# IsolatedPeltierDriver.net
KiCad netlist of a schematic drawn in Altium Designer
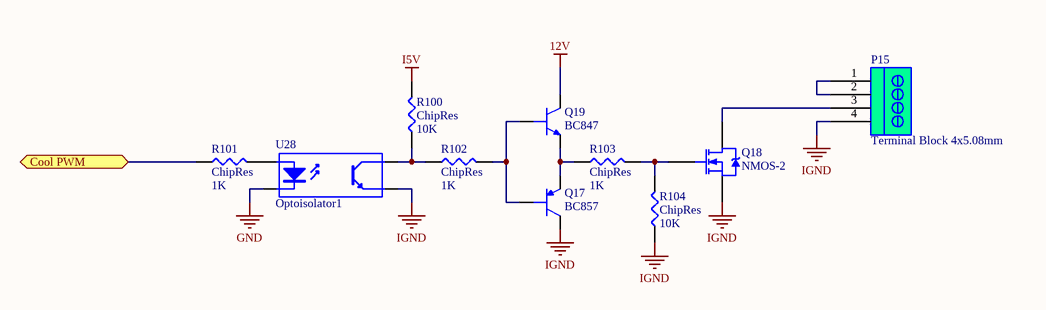
[diagram p0: IsolatedPeltierDriver.SchDoc]

(export (version "E")
  (design (tool "Eeschema 10.0.6"))
  (components
    (comp (ref "P15")
      (value "Terminal Block 4x5.08mm")
      (footprint "Socket 4x5.08")
      (description "Terminal Block Socket Right Angle 4x5.08mm 2-Wall")
      (libsource (lib "IndustrialConnectors") (part "Socket_4x5.08_RA_2Wall"))
    )
    (comp (ref "Q17")
      (value "BC857")
      (footprint "SOT23")
      (description "PNP Transistor")
      (libsource (lib "BJT") (part "BC857"))
    )
    (comp (ref "Q18")
      (value "NMOS-2")
      (footprint "TO-220")
      (description "N-Channel Power MOSFET")
      (fields (field (name "PUBLISHER") "Altium Limited"))
      (libsource (lib "Miscellaneous Devices") (part "NMOS-2"))
    )
    (comp (ref "Q19")
      (value "BC847")
      (footprint "SOT23")
      (description "NPN transistor")
      (libsource (lib "BJT") (part "BC847"))
    )
    (comp (ref "R100")
      (value "ChipRes")
      (footprint "RES0805")
      (description "Chip resistor")
      (fields (field (name "ALTIUM_VALUE") "10K"))
      (libsource (lib "Common Devices") (part "ChipRes"))
    )
    (comp (ref "R101")
      (value "ChipRes")
      (footprint "RES0805")
      (description "Chip resistor")
      (fields (field (name "ALTIUM_VALUE") "1K"))
      (libsource (lib "Common Devices") (part "ChipRes"))
    )
    (comp (ref "R102")
      (value "ChipRes")
      (footprint "RES0805")
      (description "Chip resistor")
      (fields (field (name "ALTIUM_VALUE") "1K"))
      (libsource (lib "Common Devices") (part "ChipRes"))
    )
    (comp (ref "R103")
      (value "ChipRes")
      (footprint "RES0805")
      (description "Chip resistor")
      (fields (field (name "ALTIUM_VALUE") "1K"))
      (libsource (lib "Common Devices") (part "ChipRes"))
    )
    (comp (ref "R104")
      (value "ChipRes")
      (footprint "RES0805")
      (description "Chip resistor")
      (fields (field (name "ALTIUM_VALUE") "10K"))
      (libsource (lib "Common Devices") (part "ChipRes"))
    )
    (comp (ref "U28")
      (value "Optoisolator1")
      (footprint "DIP-4")
      (description "4-Pin Phototransistor Optocoupler")
      (fields (field (name "PUBLISHER") "Altium Limited"))
      (libsource (lib "Miscellaneous Devices") (part "Optoisolator1"))
    )
  )
  (nets
    (net (code "1") (name "/Cool PWM") (class "Default") (node (ref "R101") (pin "1") (pintype "passive")))
    (net (code "2") (name "12V") (class "Default")
      (node (ref "Q19") (pin "3") (pinfunction "3_3") (pintype "passive"))
    )
    (net (code "3") (name "GND") (class "Default")
      (node (ref "U28") (pin "2") (pinfunction "K_2") (pintype "passive"))
    )
    (net (code "4") (name "I5V") (class "Default") (node (ref "R100") (pin "2") (pintype "passive")))
    (net (code "5") (name "IGND") (class "Default")
      (node (ref "P15") (pin "4") (pintype "passive"))
      (node (ref "Q17") (pin "3") (pinfunction "3_3") (pintype "passive"))
      (node (ref "Q18") (pin "3") (pinfunction "S_3") (pintype "passive"))
      (node (ref "R104") (pin "1") (pintype "passive"))
      (node (ref "U28") (pin "3") (pinfunction "E_3") (pintype "passive"))
    )
    (net (code "6") (name "Net-(P15-Pad1)") (class "Default")
      (node (ref "P15") (pin "1") (pintype "passive"))
      (node (ref "P15") (pin "2") (pintype "passive"))
    )
    (net (code "7") (name "Net-(Q17-Pad1)") (class "Default")
      (node (ref "Q17") (pin "1") (pinfunction "1_1") (pintype "passive"))
      (node (ref "Q19") (pin "1") (pinfunction "1_1") (pintype "passive"))
      (node (ref "R102") (pin "2") (pintype "passive"))
    )
    (net (code "8") (name "Net-(Q17-Pad2)") (class "Default")
      (node (ref "Q17") (pin "2") (pinfunction "2_2") (pintype "passive"))
      (node (ref "Q19") (pin "2") (pinfunction "2_2") (pintype "passive"))
      (node (ref "R103") (pin "1") (pintype "passive"))
    )
    (net (code "9") (name "Net-(Q18-D)") (class "Default")
      (node (ref "P15") (pin "3") (pintype "passive"))
      (node (ref "Q18") (pin "2") (pinfunction "D_2") (pintype "passive"))
    )
    (net (code "10") (name "Net-(Q18-G)") (class "Default")
      (node (ref "Q18") (pin "1") (pinfunction "G_1") (pintype "passive"))
      (node (ref "R103") (pin "2") (pintype "passive"))
      (node (ref "R104") (pin "2") (pintype "passive"))
    )
    (net (code "11") (name "Net-(U28-A)") (class "Default")
      (node (ref "R101") (pin "2") (pintype "passive"))
      (node (ref "U28") (pin "1") (pinfunction "A_1") (pintype "passive"))
    )
    (net (code "12") (name "Net-(U28-C)") (class "Default")
      (node (ref "R100") (pin "1") (pintype "passive"))
      (node (ref "R102") (pin "1") (pintype "passive"))
      (node (ref "U28") (pin "4") (pinfunction "C_4") (pintype "passive"))
    )
  )
)
